# M312B.net
KiCad netlist of a schematic drawn in EAGLE
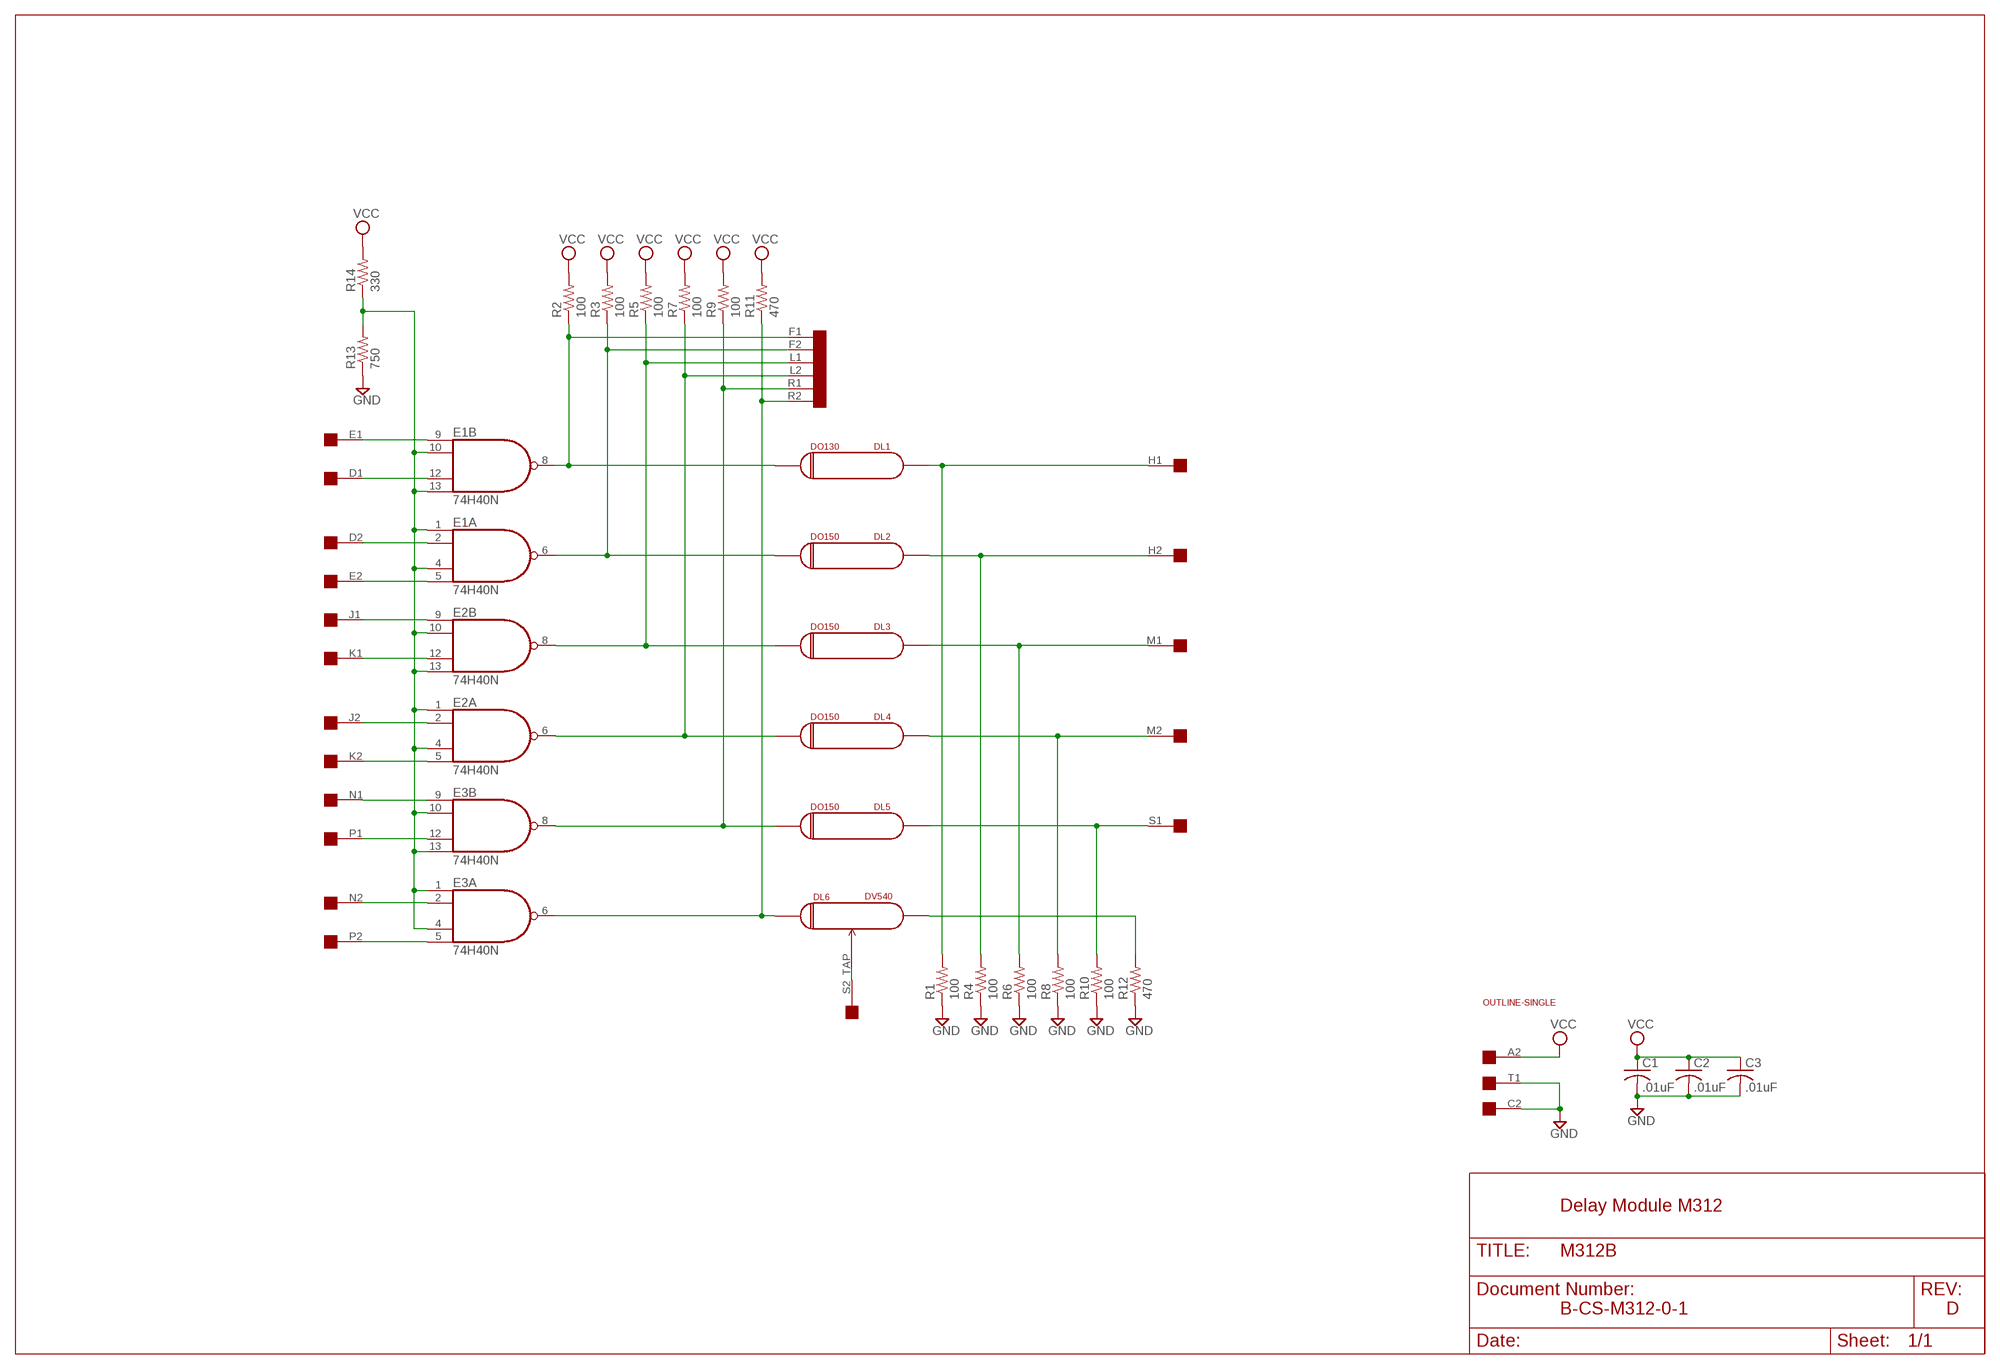
[diagram p0: schematic, sheet 1]

(export (version "E")
  (design (tool "Eeschema 10.0.6"))
  (components
    (comp (ref "C1")
      (value ".01uF")
      (footprint "eagle-import:C050-025X075")
      (libsource (lib "eagle-import") (part "C-US050-025X075"))
    )
    (comp (ref "C2")
      (value ".01uF")
      (footprint "eagle-import:C050-025X075")
      (libsource (lib "eagle-import") (part "C-US050-025X075"))
    )
    (comp (ref "C3")
      (value ".01uF")
      (footprint "eagle-import:C050-025X075")
      (libsource (lib "eagle-import") (part "C-US050-025X075"))
    )
    (comp (ref "DL1")
      (value "DO130")
      (footprint "eagle-import:RCL-L-XX-22")
      (libsource (lib "eagle-import") (part "RC-L-22"))
    )
    (comp (ref "DL2")
      (value "DO150")
      (footprint "eagle-import:RCL-L-XX-22")
      (libsource (lib "eagle-import") (part "RC-L-22"))
    )
    (comp (ref "DL3")
      (value "DO150")
      (footprint "eagle-import:RCL-L-XX-22")
      (libsource (lib "eagle-import") (part "RC-L-22"))
    )
    (comp (ref "DL4")
      (value "DO150")
      (footprint "eagle-import:RCL-L-XX-22")
      (libsource (lib "eagle-import") (part "RC-L-22"))
    )
    (comp (ref "DL5")
      (value "DO150")
      (footprint "eagle-import:RCL-L-XX-22")
      (libsource (lib "eagle-import") (part "RC-L-22"))
    )
    (comp (ref "DL6")
      (value "DV540")
      (footprint "eagle-import:DV540")
      (libsource (lib "eagle-import") (part "DV540"))
    )
    (comp (ref "E1")
      (value "74H40N")
      (footprint "eagle-import:DIL14")
      (libsource (lib "eagle-import") (part "7420NS"))
    )
    (comp (ref "E2")
      (value "74H40N")
      (footprint "eagle-import:DIL14")
      (libsource (lib "eagle-import") (part "7420NS"))
    )
    (comp (ref "E3")
      (value "74H40N")
      (footprint "eagle-import:DIL14")
      (libsource (lib "eagle-import") (part "7420NS"))
    )
    (comp (ref "R1")
      (value "100")
      (footprint "eagle-import:0207_10")
      (libsource (lib "eagle-import") (part "R-US_0207/10"))
    )
    (comp (ref "R2")
      (value "100")
      (footprint "eagle-import:0207_10")
      (libsource (lib "eagle-import") (part "R-US_0207/10"))
    )
    (comp (ref "R3")
      (value "100")
      (footprint "eagle-import:0207_10")
      (libsource (lib "eagle-import") (part "R-US_0207/10"))
    )
    (comp (ref "R4")
      (value "100")
      (footprint "eagle-import:0207_10")
      (libsource (lib "eagle-import") (part "R-US_0207/10"))
    )
    (comp (ref "R5")
      (value "100")
      (footprint "eagle-import:0207_10")
      (libsource (lib "eagle-import") (part "R-US_0207/10"))
    )
    (comp (ref "R6")
      (value "100")
      (footprint "eagle-import:0207_10")
      (libsource (lib "eagle-import") (part "R-US_0207/10"))
    )
    (comp (ref "R7")
      (value "100")
      (footprint "eagle-import:0207_10")
      (libsource (lib "eagle-import") (part "R-US_0207/10"))
    )
    (comp (ref "R8")
      (value "100")
      (footprint "eagle-import:0207_10")
      (libsource (lib "eagle-import") (part "R-US_0207/10"))
    )
    (comp (ref "R9")
      (value "100")
      (footprint "eagle-import:0207_10")
      (libsource (lib "eagle-import") (part "R-US_0207/10"))
    )
    (comp (ref "R10")
      (value "100")
      (footprint "eagle-import:0207_10")
      (libsource (lib "eagle-import") (part "R-US_0207/10"))
    )
    (comp (ref "R11")
      (value "470")
      (footprint "eagle-import:0207_10")
      (libsource (lib "eagle-import") (part "R-US_0207/10"))
    )
    (comp (ref "R12")
      (value "470")
      (footprint "eagle-import:0207_10")
      (libsource (lib "eagle-import") (part "R-US_0207/10"))
    )
    (comp (ref "R13")
      (value "750")
      (footprint "eagle-import:0207_10")
      (libsource (lib "eagle-import") (part "R-US_0207/10"))
    )
    (comp (ref "R14")
      (value "330")
      (footprint "eagle-import:0207_10")
      (libsource (lib "eagle-import") (part "R-US_0207/10"))
    )
    (comp (ref "U$1")
      (value "OUTLINE-SINGLE")
      (footprint "eagle-import:SINGLE")
      (libsource (lib "eagle-import") (part "OUTLINE-SINGLE"))
    )
    (comp (ref "U$4")
      (value "SINGLE")
      (footprint "eagle-import:EDGE-CON2")
      (libsource (lib "eagle-import") (part "SINGLE"))
    )
  )
  (nets
    (net (code "1") (name "GND") (class "Default")
      (node (ref "C1") (pin "2") (pinfunction "2_2") (pintype "passive"))
      (node (ref "C2") (pin "2") (pinfunction "2_2") (pintype "passive"))
      (node (ref "C3") (pin "2") (pinfunction "2_2") (pintype "passive"))
      (node (ref "R1") (pin "1") (pinfunction "1_1") (pintype "passive"))
      (node (ref "R10") (pin "1") (pinfunction "1_1") (pintype "passive"))
      (node (ref "R12") (pin "1") (pinfunction "1_1") (pintype "passive"))
      (node (ref "R13") (pin "1") (pinfunction "1_1") (pintype "passive"))
      (node (ref "R4") (pin "1") (pinfunction "1_1") (pintype "passive"))
      (node (ref "R6") (pin "1") (pinfunction "1_1") (pintype "passive"))
      (node (ref "R8") (pin "1") (pinfunction "1_1") (pintype "passive"))
      (node (ref "U$4") (pin "C2") (pinfunction "1_C2") (pintype "bidirectional"))
      (node (ref "U$4") (pin "T1") (pinfunction "1_T1") (pintype "bidirectional"))
    )
    (net (code "2") (name "Net-(DL6-PadOUT)") (class "Default")
      (node (ref "DL6") (pin "OUT") (pinfunction "OUT_OUT") (pintype "bidirectional"))
      (node (ref "R12") (pin "2") (pinfunction "2_2") (pintype "passive"))
    )
    (net (code "3") (name "Net-(E1A-I0)") (class "Default")
      (node (ref "E1") (pin "1") (pinfunction "I0_1") (pintype "input"))
      (node (ref "E1") (pin "10") (pinfunction "I1_10") (pintype "input"))
      (node (ref "E1") (pin "13") (pinfunction "I3_13") (pintype "input"))
      (node (ref "E1") (pin "4") (pinfunction "I2_4") (pintype "input"))
      (node (ref "E2") (pin "1") (pinfunction "I0_1") (pintype "input"))
      (node (ref "E2") (pin "10") (pinfunction "I1_10") (pintype "input"))
      (node (ref "E2") (pin "13") (pinfunction "I3_13") (pintype "input"))
      (node (ref "E2") (pin "4") (pinfunction "I2_4") (pintype "input"))
      (node (ref "E3") (pin "1") (pinfunction "I0_1") (pintype "input"))
      (node (ref "E3") (pin "10") (pinfunction "I1_10") (pintype "input"))
      (node (ref "E3") (pin "13") (pinfunction "I3_13") (pintype "input"))
      (node (ref "E3") (pin "4") (pinfunction "I2_4") (pintype "input"))
      (node (ref "R13") (pin "2") (pinfunction "2_2") (pintype "passive"))
      (node (ref "R14") (pin "1") (pinfunction "1_1") (pintype "passive"))
    )
    (net (code "4") (name "Net-(E1A-I1)") (class "Default")
      (node (ref "E1") (pin "2") (pinfunction "I1_2") (pintype "input"))
      (node (ref "U$4") (pin "D2") (pinfunction "1_D2") (pintype "bidirectional"))
    )
    (net (code "5") (name "Net-(E1A-I3)") (class "Default")
      (node (ref "E1") (pin "5") (pinfunction "I3_5") (pintype "input"))
      (node (ref "U$4") (pin "E2") (pinfunction "1_E2") (pintype "bidirectional"))
    )
    (net (code "6") (name "Net-(E1A-O)") (class "Default")
      (node (ref "DL2") (pin "OUT") (pinfunction "OUT_OUT") (pintype "bidirectional"))
      (node (ref "E1") (pin "6") (pinfunction "O_6") (pintype "output"))
      (node (ref "R3") (pin "1") (pinfunction "1_1") (pintype "passive"))
      (node (ref "U$4") (pin "F2") (pinfunction "1_F2") (pintype "bidirectional"))
    )
    (net (code "7") (name "Net-(E1B-I0)") (class "Default")
      (node (ref "E1") (pin "9") (pinfunction "I0_9") (pintype "input"))
      (node (ref "U$4") (pin "E1") (pinfunction "1_E1") (pintype "bidirectional"))
    )
    (net (code "8") (name "Net-(E1B-I2)") (class "Default")
      (node (ref "E1") (pin "12") (pinfunction "I2_12") (pintype "input"))
      (node (ref "U$4") (pin "D1") (pinfunction "1_D1") (pintype "bidirectional"))
    )
    (net (code "9") (name "Net-(E1B-O)") (class "Default")
      (node (ref "DL1") (pin "OUT") (pinfunction "OUT_OUT") (pintype "bidirectional"))
      (node (ref "E1") (pin "8") (pinfunction "O_8") (pintype "output"))
      (node (ref "R2") (pin "1") (pinfunction "1_1") (pintype "passive"))
      (node (ref "U$4") (pin "F1") (pinfunction "1_F1") (pintype "bidirectional"))
    )
    (net (code "10") (name "Net-(E2A-I1)") (class "Default")
      (node (ref "E2") (pin "2") (pinfunction "I1_2") (pintype "input"))
      (node (ref "U$4") (pin "J2") (pinfunction "1_J2") (pintype "bidirectional"))
    )
    (net (code "11") (name "Net-(E2A-I3)") (class "Default")
      (node (ref "E2") (pin "5") (pinfunction "I3_5") (pintype "input"))
      (node (ref "U$4") (pin "K2") (pinfunction "1_K2") (pintype "bidirectional"))
    )
    (net (code "12") (name "Net-(E2A-O)") (class "Default")
      (node (ref "DL4") (pin "OUT") (pinfunction "OUT_OUT") (pintype "bidirectional"))
      (node (ref "E2") (pin "6") (pinfunction "O_6") (pintype "output"))
      (node (ref "R7") (pin "1") (pinfunction "1_1") (pintype "passive"))
      (node (ref "U$4") (pin "L2") (pinfunction "1_L2") (pintype "bidirectional"))
    )
    (net (code "13") (name "Net-(E2B-I0)") (class "Default")
      (node (ref "E2") (pin "9") (pinfunction "I0_9") (pintype "input"))
      (node (ref "U$4") (pin "J1") (pinfunction "1_J1") (pintype "bidirectional"))
    )
    (net (code "14") (name "Net-(E2B-I2)") (class "Default")
      (node (ref "E2") (pin "12") (pinfunction "I2_12") (pintype "input"))
      (node (ref "U$4") (pin "K1") (pinfunction "1_K1") (pintype "bidirectional"))
    )
    (net (code "15") (name "Net-(E2B-O)") (class "Default")
      (node (ref "DL3") (pin "OUT") (pinfunction "OUT_OUT") (pintype "bidirectional"))
      (node (ref "E2") (pin "8") (pinfunction "O_8") (pintype "output"))
      (node (ref "R5") (pin "1") (pinfunction "1_1") (pintype "passive"))
      (node (ref "U$4") (pin "L1") (pinfunction "1_L1") (pintype "bidirectional"))
    )
    (net (code "16") (name "Net-(E3A-I1)") (class "Default")
      (node (ref "E3") (pin "2") (pinfunction "I1_2") (pintype "input"))
      (node (ref "U$4") (pin "N2") (pinfunction "1_N2") (pintype "bidirectional"))
    )
    (net (code "17") (name "Net-(E3A-I3)") (class "Default")
      (node (ref "E3") (pin "5") (pinfunction "I3_5") (pintype "input"))
      (node (ref "U$4") (pin "P2") (pinfunction "1_P2") (pintype "bidirectional"))
    )
    (net (code "18") (name "Net-(E3A-O)") (class "Default")
      (node (ref "DL6") (pin "IN") (pinfunction "IN_IN") (pintype "bidirectional"))
      (node (ref "E3") (pin "6") (pinfunction "O_6") (pintype "output"))
      (node (ref "R11") (pin "1") (pinfunction "1_1") (pintype "passive"))
      (node (ref "U$4") (pin "R2") (pinfunction "1_R2") (pintype "bidirectional"))
    )
    (net (code "19") (name "Net-(E3B-I0)") (class "Default")
      (node (ref "E3") (pin "9") (pinfunction "I0_9") (pintype "input"))
      (node (ref "U$4") (pin "N1") (pinfunction "1_N1") (pintype "bidirectional"))
    )
    (net (code "20") (name "Net-(E3B-I2)") (class "Default")
      (node (ref "E3") (pin "12") (pinfunction "I2_12") (pintype "input"))
      (node (ref "U$4") (pin "P1") (pinfunction "1_P1") (pintype "bidirectional"))
    )
    (net (code "21") (name "Net-(E3B-O)") (class "Default")
      (node (ref "DL5") (pin "OUT") (pinfunction "OUT_OUT") (pintype "bidirectional"))
      (node (ref "E3") (pin "8") (pinfunction "O_8") (pintype "output"))
      (node (ref "R9") (pin "1") (pinfunction "1_1") (pintype "passive"))
      (node (ref "U$4") (pin "R1") (pinfunction "1_R1") (pintype "bidirectional"))
    )
    (net (code "22") (name "Net-(U$4AC-1)") (class "Default")
      (node (ref "DL5") (pin "IN") (pinfunction "IN_IN") (pintype "bidirectional"))
      (node (ref "R10") (pin "2") (pinfunction "2_2") (pintype "passive"))
      (node (ref "U$4") (pin "S1") (pinfunction "1_S1") (pintype "bidirectional"))
    )
    (net (code "23") (name "Net-(U$4AD-1)") (class "Default")
      (node (ref "DL6") (pin "TAP") (pinfunction "TAP_TAP") (pintype "bidirectional"))
      (node (ref "U$4") (pin "S2") (pinfunction "1_S2") (pintype "bidirectional"))
    )
    (net (code "24") (name "Net-(U$4M-1)") (class "Default")
      (node (ref "DL1") (pin "IN") (pinfunction "IN_IN") (pintype "bidirectional"))
      (node (ref "R1") (pin "2") (pinfunction "2_2") (pintype "passive"))
      (node (ref "U$4") (pin "H1") (pinfunction "1_H1") (pintype "bidirectional"))
    )
    (net (code "25") (name "Net-(U$4N-1)") (class "Default")
      (node (ref "DL2") (pin "IN") (pinfunction "IN_IN") (pintype "bidirectional"))
      (node (ref "R4") (pin "2") (pinfunction "2_2") (pintype "passive"))
      (node (ref "U$4") (pin "H2") (pinfunction "1_H2") (pintype "bidirectional"))
    )
    (net (code "26") (name "Net-(U$4U-1)") (class "Default")
      (node (ref "DL3") (pin "IN") (pinfunction "IN_IN") (pintype "bidirectional"))
      (node (ref "R6") (pin "2") (pinfunction "2_2") (pintype "passive"))
      (node (ref "U$4") (pin "M1") (pinfunction "1_M1") (pintype "bidirectional"))
    )
    (net (code "27") (name "Net-(U$4V-1)") (class "Default")
      (node (ref "DL4") (pin "IN") (pinfunction "IN_IN") (pintype "bidirectional"))
      (node (ref "R8") (pin "2") (pinfunction "2_2") (pintype "passive"))
      (node (ref "U$4") (pin "M2") (pinfunction "1_M2") (pintype "bidirectional"))
    )
    (net (code "28") (name "VCC") (class "Default")
      (node (ref "C1") (pin "1") (pinfunction "1_1") (pintype "passive"))
      (node (ref "C2") (pin "1") (pinfunction "1_1") (pintype "passive"))
      (node (ref "C3") (pin "1") (pinfunction "1_1") (pintype "passive"))
      (node (ref "R11") (pin "2") (pinfunction "2_2") (pintype "passive"))
      (node (ref "R14") (pin "2") (pinfunction "2_2") (pintype "passive"))
      (node (ref "R2") (pin "2") (pinfunction "2_2") (pintype "passive"))
      (node (ref "R3") (pin "2") (pinfunction "2_2") (pintype "passive"))
      (node (ref "R5") (pin "2") (pinfunction "2_2") (pintype "passive"))
      (node (ref "R7") (pin "2") (pinfunction "2_2") (pintype "passive"))
      (node (ref "R9") (pin "2") (pinfunction "2_2") (pintype "passive"))
      (node (ref "U$4") (pin "A2") (pinfunction "1_A2") (pintype "bidirectional"))
    )
  )
)
